# sch.net
KiCad netlist of a schematic drawn in Altium Designer
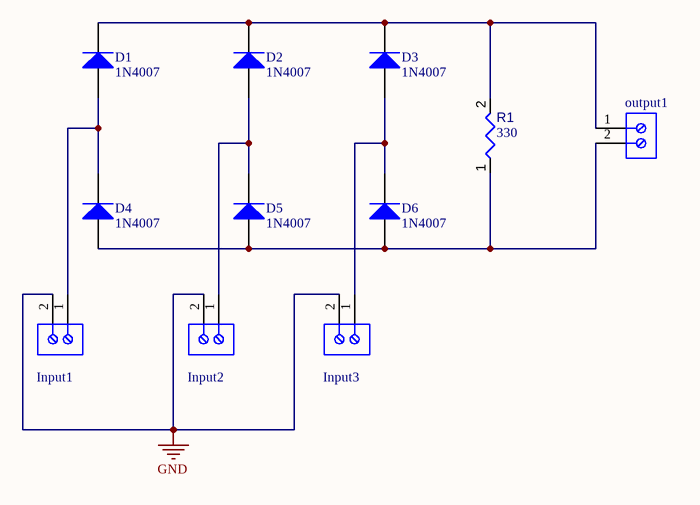
[diagram p0: sch.SchDoc]

(export (version "E")
  (design (tool "Eeschema 10.0.6"))
  (components
    (comp (ref "D1")
      (value "1N4007")
      (footprint "FAIR-DO-41-2")
      (description "General Purpose Rectifier, 1.1 V, 1.0 A, -55 to 175 degC, 2-Pin DO-41, RoHS, Tape and Reel")
      (fields (field (name "MANUFACTURER") "Fairchild"))
      (libsource (lib "Alexandria University") (part "KESE-D_K1A2-2"))
    )
    (comp (ref "D2")
      (value "1N4007")
      (footprint "FAIR-DO-41-2")
      (description "General Purpose Rectifier, 1.1 V, 1.0 A, -55 to 175 degC, 2-Pin DO-41, RoHS, Tape and Reel")
      (fields (field (name "MANUFACTURER") "Fairchild"))
      (libsource (lib "Alexandria University") (part "KESE-D_K1A2-2"))
    )
    (comp (ref "D3")
      (value "1N4007")
      (footprint "FAIR-DO-41-2")
      (description "General Purpose Rectifier, 1.1 V, 1.0 A, -55 to 175 degC, 2-Pin DO-41, RoHS, Tape and Reel")
      (fields (field (name "MANUFACTURER") "Fairchild"))
      (libsource (lib "Alexandria University") (part "KESE-D_K1A2-2"))
    )
    (comp (ref "D4")
      (value "1N4007")
      (footprint "FAIR-DO-41-2")
      (description "General Purpose Rectifier, 1.1 V, 1.0 A, -55 to 175 degC, 2-Pin DO-41, RoHS, Tape and Reel")
      (fields (field (name "MANUFACTURER") "Fairchild"))
      (libsource (lib "Alexandria University") (part "KESE-D_K1A2-2"))
    )
    (comp (ref "D5")
      (value "1N4007")
      (footprint "FAIR-DO-41-2")
      (description "General Purpose Rectifier, 1.1 V, 1.0 A, -55 to 175 degC, 2-Pin DO-41, RoHS, Tape and Reel")
      (fields (field (name "MANUFACTURER") "Fairchild"))
      (libsource (lib "Alexandria University") (part "KESE-D_K1A2-2"))
    )
    (comp (ref "D6")
      (value "1N4007")
      (footprint "FAIR-DO-41-2")
      (description "General Purpose Rectifier, 1.1 V, 1.0 A, -55 to 175 degC, 2-Pin DO-41, RoHS, Tape and Reel")
      (fields (field (name "MANUFACTURER") "Fairchild"))
      (libsource (lib "Alexandria University") (part "KESE-D_K1A2-2"))
    )
    (comp (ref "Input1")
      (value "691137710002")
      (footprint "terminals")
      (description "Series 1377 - 5.00 mm Horizontal Entry with Pressure Clamp WR-TBL, 2 pin")
      (fields (field (name "MANUFACTURER") "Wurth Elektronik") (field (name "PUBLISHER") "WurthElektronik"))
      (libsource (lib "Schlib1") (part "terminals"))
    )
    (comp (ref "Input2")
      (value "691137710002")
      (footprint "terminals")
      (description "Series 1377 - 5.00 mm Horizontal Entry with Pressure Clamp WR-TBL, 2 pin")
      (fields (field (name "MANUFACTURER") "Wurth Elektronik") (field (name "PUBLISHER") "WurthElektronik"))
      (libsource (lib "Schlib1") (part "terminals"))
    )
    (comp (ref "Input3")
      (value "691137710002")
      (footprint "terminals")
      (description "Series 1377 - 5.00 mm Horizontal Entry with Pressure Clamp WR-TBL, 2 pin")
      (fields (field (name "MANUFACTURER") "Wurth Elektronik") (field (name "PUBLISHER") "WurthElektronik"))
      (libsource (lib "Schlib1") (part "terminals"))
    )
    (comp (ref "output1")
      (value "691137710002")
      (footprint "terminals")
      (description "Series 1377 - 5.00 mm Horizontal Entry with Pressure Clamp WR-TBL, 2 pin")
      (fields (field (name "MANUFACTURER") "Wurth Elektronik") (field (name "PUBLISHER") "WurthElektronik"))
      (libsource (lib "Schlib1") (part "terminals"))
    )
    (comp (ref "R1")
      (value "330")
      (footprint "RESA60-630X240")
      (description "Axial Resistor, 221 Ohm, +/- 1%, 250 mW, -55 to 155 degC, 2-Pin THD, RoHS, Bulk")
      (fields (field (name "POWER") "250mW") (field (name "TOLERANCE") "1%"))
      (libsource (lib "Alexandria University") (part "RES-2"))
    )
  )
  (nets
    (net (code "1") (name "GND") (class "Default")
      (node (ref "Input1") (pin "2") (pinfunction "2_2") (pintype "passive"))
      (node (ref "Input2") (pin "2") (pinfunction "2_2") (pintype "passive"))
      (node (ref "Input3") (pin "2") (pinfunction "2_2") (pintype "passive"))
    )
    (net (code "2") (name "Net-(D1-A)") (class "Default")
      (node (ref "D1") (pin "2") (pinfunction "A_2") (pintype "passive"))
      (node (ref "D4") (pin "1") (pinfunction "K_1") (pintype "passive"))
      (node (ref "Input1") (pin "1") (pinfunction "1_1") (pintype "passive"))
    )
    (net (code "3") (name "Net-(D1-K)") (class "Default")
      (node (ref "D1") (pin "1") (pinfunction "K_1") (pintype "passive"))
      (node (ref "D2") (pin "1") (pinfunction "K_1") (pintype "passive"))
      (node (ref "D3") (pin "1") (pinfunction "K_1") (pintype "passive"))
      (node (ref "R1") (pin "2") (pinfunction "2_2") (pintype "passive"))
      (node (ref "output1") (pin "1") (pinfunction "1_1") (pintype "passive"))
    )
    (net (code "4") (name "Net-(D2-A)") (class "Default")
      (node (ref "D2") (pin "2") (pinfunction "A_2") (pintype "passive"))
      (node (ref "D5") (pin "1") (pinfunction "K_1") (pintype "passive"))
      (node (ref "Input2") (pin "1") (pinfunction "1_1") (pintype "passive"))
    )
    (net (code "5") (name "Net-(D3-A)") (class "Default")
      (node (ref "D3") (pin "2") (pinfunction "A_2") (pintype "passive"))
      (node (ref "D6") (pin "1") (pinfunction "K_1") (pintype "passive"))
      (node (ref "Input3") (pin "1") (pinfunction "1_1") (pintype "passive"))
    )
    (net (code "6") (name "Net-(D4-A)") (class "Default")
      (node (ref "D4") (pin "2") (pinfunction "A_2") (pintype "passive"))
      (node (ref "D5") (pin "2") (pinfunction "A_2") (pintype "passive"))
      (node (ref "D6") (pin "2") (pinfunction "A_2") (pintype "passive"))
      (node (ref "R1") (pin "1") (pinfunction "1_1") (pintype "passive"))
      (node (ref "output1") (pin "2") (pinfunction "2_2") (pintype "passive"))
    )
  )
)
